# esp-8266-test.net
KiCad netlist of a schematic drawn in EAGLE
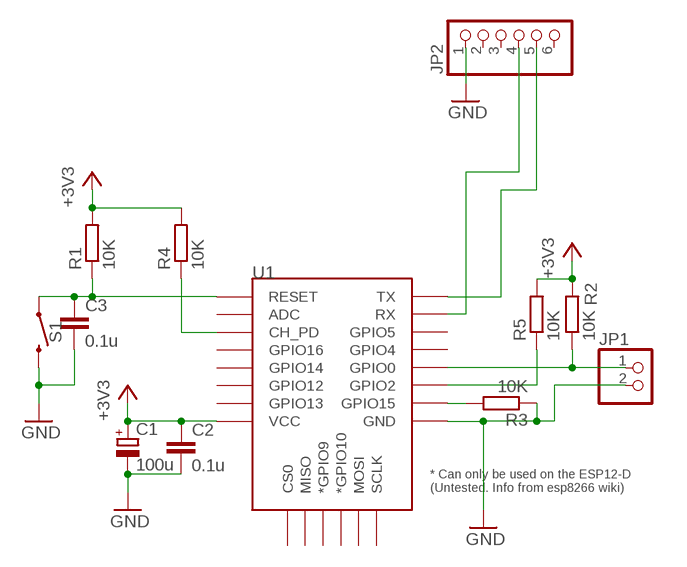
[diagram p0: schematic, sheet 1]

(export (version "E")
  (design (tool "Eeschema 10.0.6"))
  (components
    (comp (ref "C1")
      (value "100u")
      (footprint "eagle-import:085CS_1AR")
      (libsource (lib "eagle-import") (part "CPOL-EU085CS-1AR"))
    )
    (comp (ref "C2")
      (value "0.1u")
      (footprint "eagle-import:C0805")
      (libsource (lib "eagle-import") (part "C-EUC0805"))
    )
    (comp (ref "C3")
      (value "0.1u")
      (footprint "eagle-import:C0805")
      (libsource (lib "eagle-import") (part "C-EUC0805"))
    )
    (comp (ref "JP1")
      (value "PINHD-1X2")
      (footprint "eagle-import:1X02")
      (libsource (lib "eagle-import") (part "PINHD-1X2"))
    )
    (comp (ref "JP2")
      (value "PINHD-1X6")
      (footprint "eagle-import:1X06")
      (libsource (lib "eagle-import") (part "PINHD-1X6"))
    )
    (comp (ref "R1")
      (value "10K")
      (footprint "eagle-import:R0805")
      (libsource (lib "eagle-import") (part "R-EU_R0805"))
    )
    (comp (ref "R2")
      (value "10K")
      (footprint "eagle-import:R0805")
      (libsource (lib "eagle-import") (part "R-EU_R0805"))
    )
    (comp (ref "R3")
      (value "10K")
      (footprint "eagle-import:R0805")
      (libsource (lib "eagle-import") (part "R-EU_R0805"))
    )
    (comp (ref "R4")
      (value "10K")
      (footprint "eagle-import:R0805")
      (libsource (lib "eagle-import") (part "R-EU_R0805"))
    )
    (comp (ref "R5")
      (value "10K")
      (footprint "eagle-import:R0805")
      (libsource (lib "eagle-import") (part "R-EU_R0805"))
    )
    (comp (ref "S1")
      (value "MOMENTARY-SWITCH-SPST-SMD-4.6X2.8MM")
      (footprint "eagle-import:TACTILE_SWITCH_SMD_4.6X2.8MM")
      (libsource (lib "eagle-import") (part "MOMENTARY-SWITCH-SPST-SMD-4.6X2.8MM"))
    )
    (comp (ref "U1")
      (value "ESP12ESMD")
      (footprint "eagle-import:ESP12E-SMD")
      (libsource (lib "eagle-import") (part "ESP12ESMD"))
    )
  )
  (nets
    (net (code "1") (name "+3V3") (class "Default")
      (node (ref "C1") (pin "+") (pinfunction "+_+") (pintype "passive"))
      (node (ref "C2") (pin "1") (pinfunction "1_1") (pintype "passive"))
      (node (ref "R1") (pin "2") (pinfunction "2_2") (pintype "passive"))
      (node (ref "R2") (pin "2") (pinfunction "2_2") (pintype "passive"))
      (node (ref "R4") (pin "2") (pinfunction "2_2") (pintype "passive"))
      (node (ref "R5") (pin "2") (pinfunction "2_2") (pintype "passive"))
      (node (ref "U1") (pin "VCC") (pinfunction "VCC_VCC") (pintype "bidirectional"))
    )
    (net (code "2") (name "GND") (class "Default")
      (node (ref "C1") (pin "-") (pinfunction "-_-") (pintype "passive"))
      (node (ref "C2") (pin "2") (pinfunction "2_2") (pintype "passive"))
      (node (ref "C3") (pin "2") (pinfunction "2_2") (pintype "passive"))
      (node (ref "JP1") (pin "2") (pinfunction "2_2") (pintype "passive"))
      (node (ref "JP2") (pin "1") (pinfunction "1_1") (pintype "passive"))
      (node (ref "R3") (pin "1") (pinfunction "1_1") (pintype "passive"))
      (node (ref "S1") (pin "3") (pinfunction "2_3") (pintype "passive"))
      (node (ref "S1") (pin "4") (pinfunction "2_4") (pintype "passive"))
      (node (ref "U1") (pin "GND") (pinfunction "GND_GND") (pintype "bidirectional"))
    )
    (net (code "3") (name "Net-(C3-Pad1)") (class "Default")
      (node (ref "C3") (pin "1") (pinfunction "1_1") (pintype "passive"))
      (node (ref "R1") (pin "1") (pinfunction "1_1") (pintype "passive"))
      (node (ref "S1") (pin "1") (pinfunction "1_1") (pintype "passive"))
      (node (ref "S1") (pin "2") (pinfunction "1_2") (pintype "passive"))
      (node (ref "U1") (pin "RESET") (pinfunction "RESET_RESET") (pintype "bidirectional"))
    )
    (net (code "4") (name "Net-(JP1-Pad1)") (class "Default")
      (node (ref "JP1") (pin "1") (pinfunction "1_1") (pintype "passive"))
      (node (ref "R2") (pin "1") (pinfunction "1_1") (pintype "passive"))
      (node (ref "U1") (pin "GPIO0") (pinfunction "GPIO0_GPIO0") (pintype "bidirectional"))
    )
    (net (code "5") (name "Net-(R3-Pad2)") (class "Default")
      (node (ref "R3") (pin "2") (pinfunction "2_2") (pintype "passive"))
      (node (ref "U1") (pin "GPIO15") (pinfunction "GPIO15_GPIO15") (pintype "bidirectional"))
    )
    (net (code "6") (name "Net-(R4-Pad1)") (class "Default")
      (node (ref "R4") (pin "1") (pinfunction "1_1") (pintype "passive"))
      (node (ref "U1") (pin "CH_PD") (pinfunction "CH_PD_CH_PD") (pintype "bidirectional"))
    )
    (net (code "7") (name "Net-(R5-Pad1)") (class "Default")
      (node (ref "R5") (pin "1") (pinfunction "1_1") (pintype "passive"))
      (node (ref "U1") (pin "GPIO2") (pinfunction "GPIO2_GPIO2") (pintype "bidirectional"))
    )
    (net (code "8") (name "Net-(U1-RX)") (class "Default")
      (node (ref "JP2") (pin "4") (pinfunction "4_4") (pintype "passive"))
      (node (ref "U1") (pin "RXD0") (pinfunction "RX_RXD0") (pintype "bidirectional"))
    )
    (net (code "9") (name "Net-(U1-TX)") (class "Default")
      (node (ref "JP2") (pin "5") (pinfunction "5_5") (pintype "passive"))
      (node (ref "U1") (pin "TXD0") (pinfunction "TX_TXD0") (pintype "bidirectional"))
    )
    (net (code "10") (name "unconnected-(JP2-Pad2)") (class "Default")
      (node (ref "JP2") (pin "2") (pinfunction "2_2") (pintype "passive"))
    )
    (net (code "11") (name "unconnected-(JP2-Pad3)") (class "Default")
      (node (ref "JP2") (pin "3") (pinfunction "3_3") (pintype "passive"))
    )
    (net (code "12") (name "unconnected-(JP2-Pad6)") (class "Default")
      (node (ref "JP2") (pin "6") (pinfunction "6_6") (pintype "passive"))
    )
    (net (code "13") (name "unconnected-(U1-*GPIO9-PadGPIO9)") (class "Default")
      (node (ref "U1") (pin "GPIO9") (pinfunction "*GPIO9_GPIO9") (pintype "bidirectional"))
    )
    (net (code "14") (name "unconnected-(U1-*GPIO10-PadGPIO10)") (class "Default")
      (node (ref "U1") (pin "GPIO10") (pinfunction "*GPIO10_GPIO10") (pintype "bidirectional"))
    )
    (net (code "15") (name "unconnected-(U1-PadADC)") (class "Default")
      (node (ref "U1") (pin "ADC") (pinfunction "ADC_ADC") (pintype "bidirectional"))
    )
    (net (code "16") (name "unconnected-(U1-PadCS0)") (class "Default")
      (node (ref "U1") (pin "CS0") (pinfunction "CS0_CS0") (pintype "bidirectional"))
    )
    (net (code "17") (name "unconnected-(U1-PadGPIO4)") (class "Default")
      (node (ref "U1") (pin "GPIO4") (pinfunction "GPIO4_GPIO4") (pintype "bidirectional"))
    )
    (net (code "18") (name "unconnected-(U1-PadGPIO5)") (class "Default")
      (node (ref "U1") (pin "GPIO5") (pinfunction "GPIO5_GPIO5") (pintype "bidirectional"))
    )
    (net (code "19") (name "unconnected-(U1-PadGPIO12)") (class "Default")
      (node (ref "U1") (pin "GPIO12") (pinfunction "GPIO12_GPIO12") (pintype "bidirectional"))
    )
    (net (code "20") (name "unconnected-(U1-PadGPIO13)") (class "Default")
      (node (ref "U1") (pin "GPIO13") (pinfunction "GPIO13_GPIO13") (pintype "bidirectional"))
    )
    (net (code "21") (name "unconnected-(U1-PadGPIO14)") (class "Default")
      (node (ref "U1") (pin "GPIO14") (pinfunction "GPIO14_GPIO14") (pintype "bidirectional"))
    )
    (net (code "22") (name "unconnected-(U1-PadGPIO16)") (class "Default")
      (node (ref "U1") (pin "GPIO16") (pinfunction "GPIO16_GPIO16") (pintype "bidirectional"))
    )
    (net (code "23") (name "unconnected-(U1-PadMISO)") (class "Default")
      (node (ref "U1") (pin "MISO") (pinfunction "MISO_MISO") (pintype "bidirectional"))
    )
    (net (code "24") (name "unconnected-(U1-PadMOSI)") (class "Default")
      (node (ref "U1") (pin "MOSI") (pinfunction "MOSI_MOSI") (pintype "bidirectional"))
    )
    (net (code "25") (name "unconnected-(U1-PadSCLK)") (class "Default")
      (node (ref "U1") (pin "SCLK") (pinfunction "SCLK_SCLK") (pintype "bidirectional"))
    )
  )
)
